# motorcontrol_v2.net
KiCad netlist of a schematic drawn in EAGLE
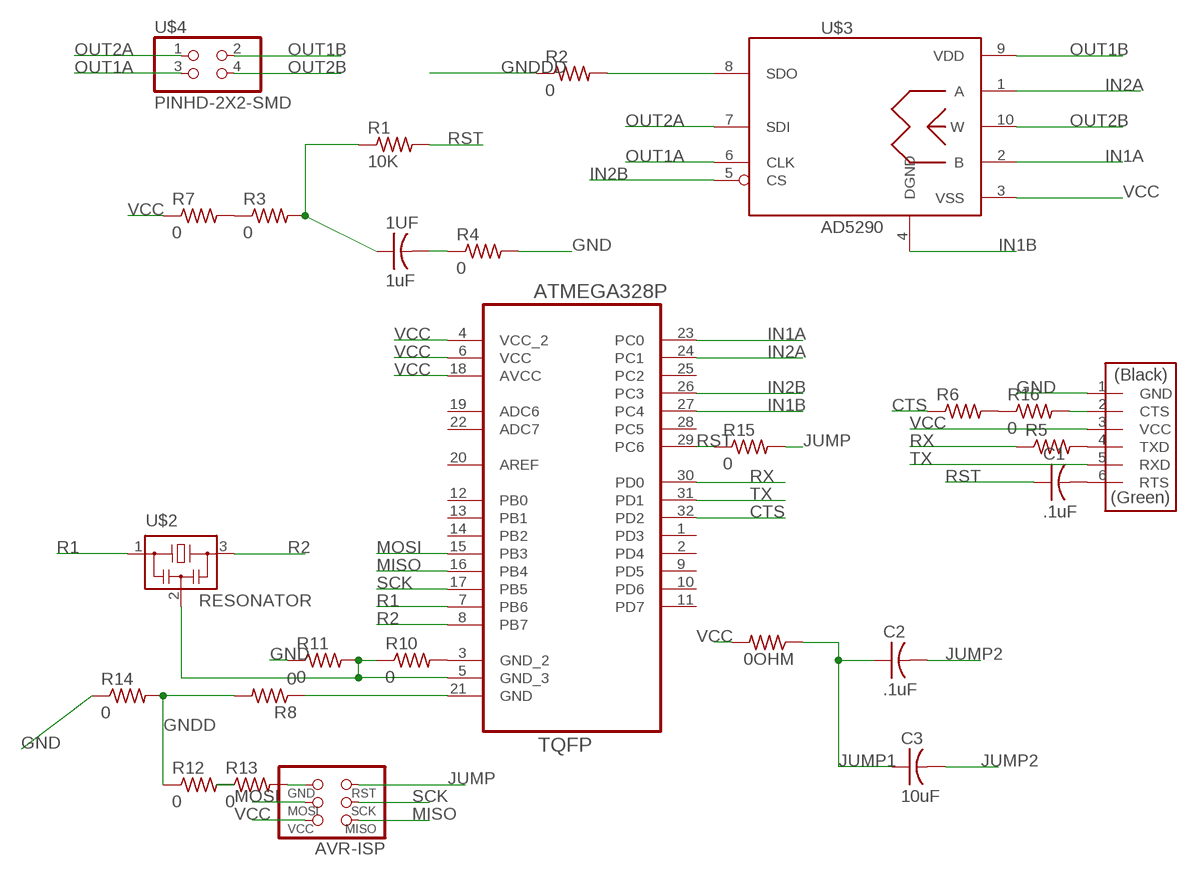
[diagram p0: schematic, sheet 1]

(export (version "E")
  (design (tool "Eeschema 10.0.6"))
  (components
    (comp (ref "0OHM")
      (value "RES-US1206FAB")
      (footprint "eagle-import:R1206FAB")
      (libsource (lib "eagle-import") (part "RES-US1206FAB"))
    )
    (comp (ref "1UF")
      (value "1uF")
      (footprint "eagle-import:C1206FAB")
      (libsource (lib "eagle-import") (part "CAP-US1206FAB"))
    )
    (comp (ref "AVR-ISP")
      (value "AVRISPSMD")
      (footprint "eagle-import:2X03SMD")
      (libsource (lib "eagle-import") (part "AVRISPSMD"))
    )
    (comp (ref "C1")
      (value ".1uF")
      (footprint "eagle-import:C1206FAB")
      (libsource (lib "eagle-import") (part "CAP-US1206FAB"))
    )
    (comp (ref "C2")
      (value ".1uF")
      (footprint "eagle-import:C1206FAB")
      (libsource (lib "eagle-import") (part "CAP-US1206FAB"))
    )
    (comp (ref "C3")
      (value "10uF")
      (footprint "eagle-import:C1206FAB")
      (libsource (lib "eagle-import") (part "CAP-US1206FAB"))
    )
    (comp (ref "R1")
      (value "10K")
      (footprint "eagle-import:R1206FAB")
      (libsource (lib "eagle-import") (part "RES-US1206FAB"))
    )
    (comp (ref "R2")
      (value "0")
      (footprint "eagle-import:R1206FAB")
      (libsource (lib "eagle-import") (part "RES-US1206FAB"))
    )
    (comp (ref "R3")
      (value "0")
      (footprint "eagle-import:R1206FAB")
      (libsource (lib "eagle-import") (part "RES-US1206FAB"))
    )
    (comp (ref "R4")
      (value "0")
      (footprint "eagle-import:R1206FAB")
      (libsource (lib "eagle-import") (part "RES-US1206FAB"))
    )
    (comp (ref "R5")
      (value "RES-US1206FAB")
      (footprint "eagle-import:R1206FAB")
      (libsource (lib "eagle-import") (part "RES-US1206FAB"))
    )
    (comp (ref "R6")
      (value "RES-US1206FAB")
      (footprint "eagle-import:R1206FAB")
      (libsource (lib "eagle-import") (part "RES-US1206FAB"))
    )
    (comp (ref "R7")
      (value "0")
      (footprint "eagle-import:R1206FAB")
      (libsource (lib "eagle-import") (part "RES-US1206FAB"))
    )
    (comp (ref "R8")
      (value "0")
      (footprint "eagle-import:R1206FAB")
      (libsource (lib "eagle-import") (part "RES-US1206FAB"))
    )
    (comp (ref "R10")
      (value "0")
      (footprint "eagle-import:R1206FAB")
      (libsource (lib "eagle-import") (part "RES-US1206FAB"))
    )
    (comp (ref "R11")
      (value "0")
      (footprint "eagle-import:R1206FAB")
      (libsource (lib "eagle-import") (part "RES-US1206FAB"))
    )
    (comp (ref "R12")
      (value "0")
      (footprint "eagle-import:R1206")
      (libsource (lib "eagle-import") (part "RES-US1206"))
    )
    (comp (ref "R13")
      (value "0")
      (footprint "eagle-import:R1206")
      (libsource (lib "eagle-import") (part "RES-US1206"))
    )
    (comp (ref "R14")
      (value "0")
      (footprint "eagle-import:R1206FAB")
      (libsource (lib "eagle-import") (part "RES-US1206FAB"))
    )
    (comp (ref "R15")
      (value "0")
      (footprint "eagle-import:R1206FAB")
      (libsource (lib "eagle-import") (part "RES-US1206FAB"))
    )
    (comp (ref "R16")
      (value "0")
      (footprint "eagle-import:R1206FAB")
      (libsource (lib "eagle-import") (part "RES-US1206FAB"))
    )
    (comp (ref "U$1")
      (value "FTDI-SMD-HEADER")
      (footprint "eagle-import:1X06SMD")
      (libsource (lib "eagle-import") (part "FTDI-SMD-HEADER"))
    )
    (comp (ref "U$2")
      (value "RESONATOR")
      (footprint "eagle-import:EFOBM")
      (libsource (lib "eagle-import") (part "RESONATOR"))
    )
    (comp (ref "U$3")
      (value "AD5290")
      (footprint "eagle-import:MSOP_10")
      (libsource (lib "eagle-import") (part "AD5290"))
    )
    (comp (ref "U$4")
      (value "PINHD-2X2-SMD")
      (footprint "eagle-import:2X02SMD")
      (libsource (lib "eagle-import") (part "PINHD-2X2-SMD"))
    )
    (comp (ref "U1")
      (value "ATMEGA328P-AU")
      (footprint "eagle-import:QFP80P900X900X120-32N")
      (libsource (lib "eagle-import") (part "ATMEGA328P-AU"))
    )
  )
  (nets
    (net (code "1") (name "/CTS") (class "Default")
      (node (ref "R6") (pin "1") (pinfunction "1_1") (pintype "passive"))
      (node (ref "U1") (pin "32") (pinfunction "PD2_32") (pintype "bidirectional"))
    )
    (net (code "2") (name "/GND") (class "Default")
      (node (ref "R11") (pin "1") (pinfunction "1_1") (pintype "passive"))
      (node (ref "R14") (pin "1") (pinfunction "1_1") (pintype "passive"))
      (node (ref "R4") (pin "2") (pinfunction "2_2") (pintype "passive"))
      (node (ref "U$1") (pin "1") (pinfunction "GND_1") (pintype "bidirectional"))
    )
    (net (code "3") (name "/GNDD") (class "Default")
      (node (ref "R12") (pin "1") (pinfunction "1_1") (pintype "passive"))
      (node (ref "R14") (pin "2") (pinfunction "2_2") (pintype "passive"))
      (node (ref "R8") (pin "2") (pinfunction "2_2") (pintype "passive"))
    )
    (net (code "4") (name "/GNDDD") (class "Default")
      (node (ref "R2") (pin "1") (pinfunction "1_1") (pintype "passive"))
      (node (ref "R8") (pin "1") (pinfunction "1_1") (pintype "passive"))
      (node (ref "U1") (pin "21") (pinfunction "GND_21") (pintype "passive"))
    )
    (net (code "5") (name "/IN1A") (class "Default")
      (node (ref "U$3") (pin "2") (pinfunction "B_2") (pintype "bidirectional"))
      (node (ref "U1") (pin "23") (pinfunction "PC0_23") (pintype "bidirectional"))
    )
    (net (code "6") (name "/IN1B") (class "Default")
      (node (ref "U$3") (pin "4") (pinfunction "DGND_4") (pintype "bidirectional"))
      (node (ref "U1") (pin "27") (pinfunction "PC4_27") (pintype "bidirectional"))
    )
    (net (code "7") (name "/IN2A") (class "Default")
      (node (ref "U$3") (pin "1") (pinfunction "A_1") (pintype "bidirectional"))
      (node (ref "U1") (pin "24") (pinfunction "PC1_24") (pintype "bidirectional"))
    )
    (net (code "8") (name "/IN2B") (class "Default")
      (node (ref "U$3") (pin "5") (pinfunction "CS_5") (pintype "input"))
      (node (ref "U1") (pin "26") (pinfunction "PC3_26") (pintype "bidirectional"))
    )
    (net (code "9") (name "/JUMP") (class "Default")
      (node (ref "AVR-ISP") (pin "5") (pinfunction "RST_5") (pintype "passive"))
      (node (ref "R15") (pin "2") (pinfunction "2_2") (pintype "passive"))
    )
    (net (code "10") (name "/JUMP1") (class "Default")
      (node (ref "0OHM") (pin "1") (pinfunction "1_1") (pintype "passive"))
      (node (ref "C2") (pin "1") (pinfunction "1_1") (pintype "passive"))
      (node (ref "C3") (pin "1") (pinfunction "1_1") (pintype "passive"))
    )
    (net (code "11") (name "/JUMP2") (class "Default")
      (node (ref "C2") (pin "2") (pinfunction "2_2") (pintype "passive"))
      (node (ref "C3") (pin "2") (pinfunction "2_2") (pintype "passive"))
      (node (ref "R2") (pin "2") (pinfunction "2_2") (pintype "passive"))
      (node (ref "U$3") (pin "8") (pinfunction "SDO_8") (pintype "bidirectional"))
    )
    (net (code "12") (name "/MISO") (class "Default")
      (node (ref "AVR-ISP") (pin "1") (pinfunction "MISO_1") (pintype "passive"))
      (node (ref "U1") (pin "16") (pinfunction "PB4_16") (pintype "bidirectional"))
    )
    (net (code "13") (name "/MOSI") (class "Default")
      (node (ref "AVR-ISP") (pin "4") (pinfunction "MOSI_4") (pintype "passive"))
      (node (ref "U1") (pin "15") (pinfunction "PB3_15") (pintype "bidirectional"))
    )
    (net (code "14") (name "/OUT1A") (class "Default")
      (node (ref "U$3") (pin "6") (pinfunction "CLK_6") (pintype "bidirectional"))
      (node (ref "U$4") (pin "3") (pinfunction "3_3") (pintype "passive"))
    )
    (net (code "15") (name "/OUT1B") (class "Default")
      (node (ref "U$3") (pin "9") (pinfunction "VDD_9") (pintype "bidirectional"))
      (node (ref "U$4") (pin "2") (pinfunction "2_2") (pintype "passive"))
    )
    (net (code "16") (name "/OUT2A") (class "Default")
      (node (ref "U$3") (pin "7") (pinfunction "SDI_7") (pintype "bidirectional"))
      (node (ref "U$4") (pin "1") (pinfunction "1_1") (pintype "passive"))
    )
    (net (code "17") (name "/OUT2B") (class "Default")
      (node (ref "U$3") (pin "10") (pinfunction "W_10") (pintype "bidirectional"))
      (node (ref "U$4") (pin "4") (pinfunction "4_4") (pintype "passive"))
    )
    (net (code "18") (name "/R1") (class "Default")
      (node (ref "U$2") (pin "1") (pinfunction "1_1") (pintype "passive"))
      (node (ref "U1") (pin "7") (pinfunction "PB6_7") (pintype "bidirectional"))
    )
    (net (code "19") (name "/R2") (class "Default")
      (node (ref "U$2") (pin "3") (pinfunction "3_3") (pintype "passive"))
      (node (ref "U1") (pin "8") (pinfunction "PB7_8") (pintype "bidirectional"))
    )
    (net (code "20") (name "/RST") (class "Default")
      (node (ref "C1") (pin "1") (pinfunction "1_1") (pintype "passive"))
      (node (ref "R1") (pin "2") (pinfunction "2_2") (pintype "passive"))
      (node (ref "R15") (pin "1") (pinfunction "1_1") (pintype "passive"))
      (node (ref "U1") (pin "29") (pinfunction "PC6_29") (pintype "bidirectional"))
    )
    (net (code "21") (name "/RX") (class "Default")
      (node (ref "R5") (pin "1") (pinfunction "1_1") (pintype "passive"))
      (node (ref "U1") (pin "30") (pinfunction "PD0_30") (pintype "bidirectional"))
    )
    (net (code "22") (name "/SCK") (class "Default")
      (node (ref "AVR-ISP") (pin "3") (pinfunction "SCK_3") (pintype "passive"))
      (node (ref "U1") (pin "17") (pinfunction "PB5_17") (pintype "bidirectional"))
    )
    (net (code "23") (name "/TX") (class "Default")
      (node (ref "U$1") (pin "5") (pinfunction "RXD_5") (pintype "bidirectional"))
      (node (ref "U1") (pin "31") (pinfunction "PD1_31") (pintype "bidirectional"))
    )
    (net (code "24") (name "/VCC") (class "Default")
      (node (ref "0OHM") (pin "2") (pinfunction "2_2") (pintype "passive"))
      (node (ref "AVR-ISP") (pin "2") (pinfunction "VCC_2") (pintype "passive"))
      (node (ref "R7") (pin "1") (pinfunction "1_1") (pintype "passive"))
      (node (ref "U$1") (pin "3") (pinfunction "VCC_3") (pintype "bidirectional"))
      (node (ref "U$3") (pin "3") (pinfunction "VSS_3") (pintype "bidirectional"))
      (node (ref "U1") (pin "18") (pinfunction "AVCC_18") (pintype "power_in"))
      (node (ref "U1") (pin "4") (pinfunction "VCC_2_4") (pintype "power_in"))
      (node (ref "U1") (pin "6") (pinfunction "VCC_6") (pintype "power_in"))
    )
    (net (code "25") (name "Net-(1UF-Pad1)") (class "Default")
      (node (ref "1UF") (pin "1") (pinfunction "1_1") (pintype "passive"))
      (node (ref "R1") (pin "1") (pinfunction "1_1") (pintype "passive"))
      (node (ref "R3") (pin "2") (pinfunction "2_2") (pintype "passive"))
    )
    (net (code "26") (name "Net-(1UF-Pad2)") (class "Default")
      (node (ref "1UF") (pin "2") (pinfunction "2_2") (pintype "passive"))
      (node (ref "R4") (pin "1") (pinfunction "1_1") (pintype "passive"))
    )
    (net (code "27") (name "Net-(AVR-ISP-GND)") (class "Default")
      (node (ref "AVR-ISP") (pin "6") (pinfunction "GND_6") (pintype "passive"))
      (node (ref "R13") (pin "2") (pinfunction "2_2") (pintype "passive"))
    )
    (net (code "28") (name "Net-(R3-Pad1)") (class "Default")
      (node (ref "R3") (pin "1") (pinfunction "1_1") (pintype "passive"))
      (node (ref "R7") (pin "2") (pinfunction "2_2") (pintype "passive"))
    )
    (net (code "29") (name "Net-(R12-Pad2)") (class "Default")
      (node (ref "R12") (pin "2") (pinfunction "2_2") (pintype "passive"))
      (node (ref "R13") (pin "1") (pinfunction "1_1") (pintype "passive"))
    )
    (net (code "30") (name "Net-(R16-Pad1)") (class "Default")
      (node (ref "R16") (pin "1") (pinfunction "1_1") (pintype "passive"))
      (node (ref "R6") (pin "2") (pinfunction "2_2") (pintype "passive"))
    )
    (net (code "31") (name "Net-(U$1-CTS)") (class "Default")
      (node (ref "R16") (pin "2") (pinfunction "2_2") (pintype "passive"))
      (node (ref "U$1") (pin "2") (pinfunction "CTS_2") (pintype "bidirectional"))
    )
    (net (code "32") (name "Net-(U$1-RTS)") (class "Default")
      (node (ref "C1") (pin "2") (pinfunction "2_2") (pintype "passive"))
      (node (ref "U$1") (pin "6") (pinfunction "RTS_6") (pintype "bidirectional"))
    )
    (net (code "33") (name "Net-(U$1-TXD)") (class "Default")
      (node (ref "R5") (pin "2") (pinfunction "2_2") (pintype "passive"))
      (node (ref "U$1") (pin "4") (pinfunction "TXD_4") (pintype "bidirectional"))
    )
    (net (code "34") (name "Net-(U1-GND_2)") (class "Default")
      (node (ref "R10") (pin "2") (pinfunction "2_2") (pintype "passive"))
      (node (ref "U1") (pin "3") (pinfunction "GND_2_3") (pintype "passive"))
    )
    (net (code "35") (name "Net-(U1-GND_3)") (class "Default")
      (node (ref "R10") (pin "1") (pinfunction "1_1") (pintype "passive"))
      (node (ref "R11") (pin "2") (pinfunction "2_2") (pintype "passive"))
      (node (ref "U$2") (pin "2") (pinfunction "2_2") (pintype "passive"))
      (node (ref "U1") (pin "5") (pinfunction "GND_3_5") (pintype "passive"))
    )
    (net (code "36") (name "unconnected-(U1-ADC6-Pad19)") (class "Default")
      (node (ref "U1") (pin "19") (pinfunction "ADC6_19") (pintype "input"))
    )
    (net (code "37") (name "unconnected-(U1-ADC7-Pad22)") (class "Default")
      (node (ref "U1") (pin "22") (pinfunction "ADC7_22") (pintype "input"))
    )
    (net (code "38") (name "unconnected-(U1-AREF-Pad20)") (class "Default")
      (node (ref "U1") (pin "20") (pinfunction "AREF_20") (pintype "input"))
    )
    (net (code "39") (name "unconnected-(U1-PB0-Pad12)") (class "Default")
      (node (ref "U1") (pin "12") (pinfunction "PB0_12") (pintype "bidirectional"))
    )
    (net (code "40") (name "unconnected-(U1-PB1-Pad13)") (class "Default")
      (node (ref "U1") (pin "13") (pinfunction "PB1_13") (pintype "bidirectional"))
    )
    (net (code "41") (name "unconnected-(U1-PB2-Pad14)") (class "Default")
      (node (ref "U1") (pin "14") (pinfunction "PB2_14") (pintype "bidirectional"))
    )
    (net (code "42") (name "unconnected-(U1-PC2-Pad25)") (class "Default")
      (node (ref "U1") (pin "25") (pinfunction "PC2_25") (pintype "bidirectional"))
    )
    (net (code "43") (name "unconnected-(U1-PC5-Pad28)") (class "Default")
      (node (ref "U1") (pin "28") (pinfunction "PC5_28") (pintype "bidirectional"))
    )
    (net (code "44") (name "unconnected-(U1-PD3-Pad1)") (class "Default")
      (node (ref "U1") (pin "1") (pinfunction "PD3_1") (pintype "bidirectional"))
    )
    (net (code "45") (name "unconnected-(U1-PD4-Pad2)") (class "Default")
      (node (ref "U1") (pin "2") (pinfunction "PD4_2") (pintype "bidirectional"))
    )
    (net (code "46") (name "unconnected-(U1-PD5-Pad9)") (class "Default")
      (node (ref "U1") (pin "9") (pinfunction "PD5_9") (pintype "bidirectional"))
    )
    (net (code "47") (name "unconnected-(U1-PD6-Pad10)") (class "Default")
      (node (ref "U1") (pin "10") (pinfunction "PD6_10") (pintype "bidirectional"))
    )
    (net (code "48") (name "unconnected-(U1-PD7-Pad11)") (class "Default")
      (node (ref "U1") (pin "11") (pinfunction "PD7_11") (pintype "bidirectional"))
    )
  )
)
